# usb_serial.net
KiCad netlist of a schematic drawn in Altium Designer
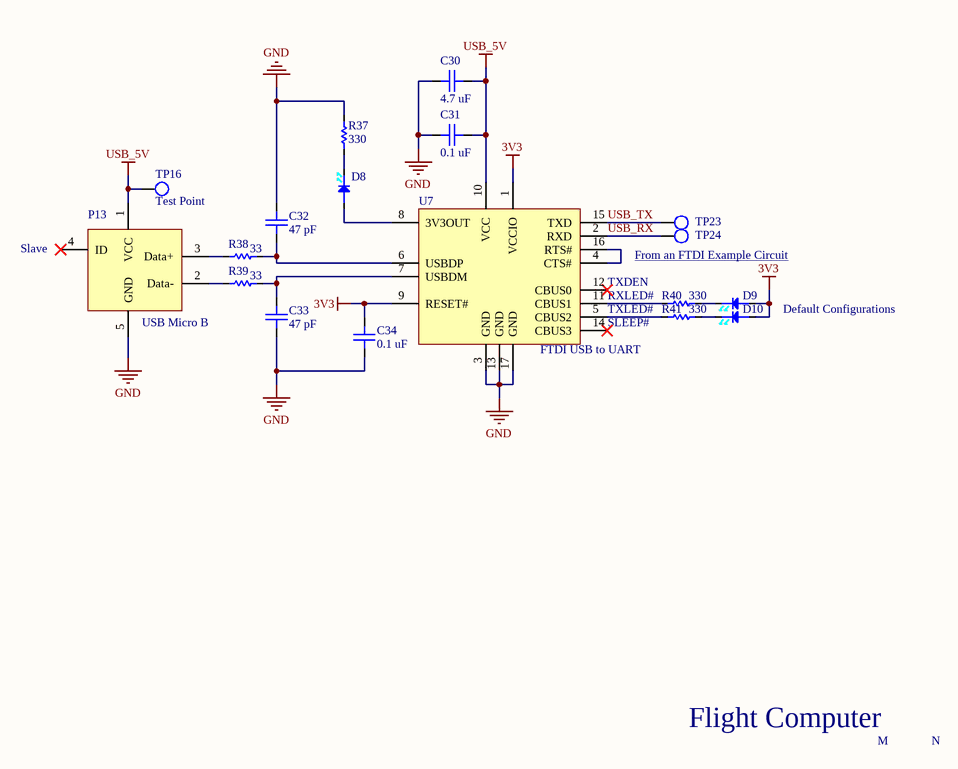
[diagram p0: usb_serial.SchDoc]

(export (version "E")
  (design (tool "Eeschema 10.0.6"))
  (components
    (comp (ref "C30")
      (value "4.7 uF")
      (footprint "CAP-CER-0805-TALL")
      (description "±10%, 0805")
      (libsource (lib "passive") (part "CAP-CER-4.7uF-10V"))
    )
    (comp (ref "C31")
      (value "0.1 uF")
      (footprint "CAP-CER-0805-SHORT")
      (description "±10%, 0805")
      (libsource (lib "passive") (part "CAP-CER-0.1uF-25V"))
    )
    (comp (ref "C32")
      (value "47 pF")
      (footprint "CAP-CER-0805-SHORT")
      (description "±5%, 0805")
      (libsource (lib "passive") (part "CAP-CER-47pF-50V"))
    )
    (comp (ref "C33")
      (value "47 pF")
      (footprint "CAP-CER-0805-SHORT")
      (description "±5%, 0805")
      (libsource (lib "passive") (part "CAP-CER-47pF-50V"))
    )
    (comp (ref "C34")
      (value "0.1 uF")
      (footprint "CAP-CER-0805-SHORT")
      (description "±10%, 0805")
      (libsource (lib "passive") (part "CAP-CER-0.1uF-25V"))
    )
    (comp (ref "D8")
      (value "LED-WHT-20mA")
      (footprint "LED-0805")
      (description "2.2V, 0805")
      (libsource (lib "passive") (part "LED-WHT-20mA"))
    )
    (comp (ref "D9")
      (value "LED-WHT-20mA")
      (footprint "LED-0805")
      (description "2.2V, 0805")
      (libsource (lib "passive") (part "LED-WHT-20mA"))
    )
    (comp (ref "D10")
      (value "LED-WHT-20mA")
      (footprint "LED-0805")
      (description "2.2V, 0805")
      (libsource (lib "passive") (part "LED-WHT-20mA"))
    )
    (comp (ref "P13")
      (value "USB Micro B")
      (footprint "USB Micro B")
      (libsource (lib "connector") (part "USB Micro B"))
    )
    (comp (ref "R37")
      (value "330")
      (footprint "RES-0805")
      (description "0805")
      (libsource (lib "passive") (part "RES-330-1/8W"))
    )
    (comp (ref "R38")
      (value "33")
      (footprint "RES-0805")
      (description "0805")
      (libsource (lib "passive") (part "RES-33-1/8W"))
    )
    (comp (ref "R39")
      (value "33")
      (footprint "RES-0805")
      (description "0805")
      (libsource (lib "passive") (part "RES-33-1/8W"))
    )
    (comp (ref "R40")
      (value "330")
      (footprint "RES-0805")
      (description "0805")
      (libsource (lib "passive") (part "RES-330-1/8W"))
    )
    (comp (ref "R41")
      (value "330")
      (footprint "RES-0805")
      (description "0805")
      (libsource (lib "passive") (part "RES-330-1/8W"))
    )
    (comp (ref "TP16")
      (value "Test Point")
      (footprint "0603 Test Point")
      (description "0603")
      (libsource (lib "passive") (part "Test Point"))
    )
    (comp (ref "TP23")
      (value "Test Point")
      (footprint "0603 Test Point")
      (description "0603")
      (libsource (lib "passive") (part "Test Point"))
    )
    (comp (ref "TP24")
      (value "Test Point")
      (footprint "0603 Test Point")
      (description "0603")
      (libsource (lib "passive") (part "Test Point"))
    )
    (comp (ref "U7")
      (value "FTDI USB to UART")
      (footprint "QFN16-0.65")
      (libsource (lib "ic") (part "FT230XQ-R"))
    )
  )
  (nets
    (net (code "1") (name "/USB_RX") (class "Default")
      (node (ref "TP24") (pin "1") (pinfunction "1_1") (pintype "passive"))
      (node (ref "U7") (pin "2") (pinfunction "RXD_2") (pintype "passive"))
    )
    (net (code "2") (name "/USB_TX") (class "Default")
      (node (ref "TP23") (pin "1") (pinfunction "1_1") (pintype "passive"))
      (node (ref "U7") (pin "15") (pinfunction "TXD_15") (pintype "passive"))
    )
    (net (code "3") (name "3V3") (class "Default")
      (node (ref "C34") (pin "2") (pinfunction "2_2") (pintype "passive"))
      (node (ref "D10") (pin "1") (pinfunction "CT_1") (pintype "passive"))
      (node (ref "D9") (pin "1") (pinfunction "CT_1") (pintype "passive"))
      (node (ref "U7") (pin "1") (pinfunction "VCCIO_1") (pintype "passive"))
      (node (ref "U7") (pin "9") (pinfunction "RESET#_9") (pintype "passive"))
    )
    (net (code "4") (name "GND") (class "Default")
      (node (ref "C30") (pin "2") (pinfunction "2_2") (pintype "passive"))
      (node (ref "C31") (pin "2") (pinfunction "2_2") (pintype "passive"))
      (node (ref "C32") (pin "2") (pinfunction "2_2") (pintype "passive"))
      (node (ref "C33") (pin "1") (pinfunction "1_1") (pintype "passive"))
      (node (ref "C34") (pin "1") (pinfunction "1_1") (pintype "passive"))
      (node (ref "P13") (pin "5") (pinfunction "GND_5") (pintype "passive"))
      (node (ref "R37") (pin "1") (pinfunction "1_1") (pintype "passive"))
      (node (ref "U7") (pin "13") (pinfunction "GND_13") (pintype "passive"))
      (node (ref "U7") (pin "17") (pinfunction "GND_17") (pintype "passive"))
      (node (ref "U7") (pin "3") (pinfunction "GND_3") (pintype "passive"))
    )
    (net (code "5") (name "Net-(D8-AN)") (class "Default")
      (node (ref "D8") (pin "2") (pinfunction "AN_2") (pintype "passive"))
      (node (ref "R37") (pin "2") (pinfunction "2_2") (pintype "passive"))
    )
    (net (code "6") (name "Net-(D8-CT)") (class "Default")
      (node (ref "D8") (pin "1") (pinfunction "CT_1") (pintype "passive"))
      (node (ref "U7") (pin "8") (pinfunction "3V3OUT_8") (pintype "passive"))
    )
    (net (code "7") (name "Net-(D9-AN)") (class "Default")
      (node (ref "D9") (pin "2") (pinfunction "AN_2") (pintype "passive"))
      (node (ref "R40") (pin "2") (pinfunction "2_2") (pintype "passive"))
    )
    (net (code "8") (name "Net-(D10-AN)") (class "Default")
      (node (ref "D10") (pin "2") (pinfunction "AN_2") (pintype "passive"))
      (node (ref "R41") (pin "2") (pinfunction "2_2") (pintype "passive"))
    )
    (net (code "9") (name "Net-(P13-Data+)") (class "Default")
      (node (ref "P13") (pin "3") (pinfunction "Data+_3") (pintype "passive"))
      (node (ref "R38") (pin "1") (pinfunction "1_1") (pintype "passive"))
    )
    (net (code "10") (name "Net-(P13-Data-)") (class "Default")
      (node (ref "P13") (pin "2") (pinfunction "Data-_2") (pintype "passive"))
      (node (ref "R39") (pin "1") (pinfunction "1_1") (pintype "passive"))
    )
    (net (code "11") (name "Net-(U7-CBUS1)") (class "Default")
      (node (ref "R40") (pin "1") (pinfunction "1_1") (pintype "passive"))
      (node (ref "U7") (pin "11") (pinfunction "CBUS1_11") (pintype "passive"))
    )
    (net (code "12") (name "Net-(U7-CBUS2)") (class "Default")
      (node (ref "R41") (pin "1") (pinfunction "1_1") (pintype "passive"))
      (node (ref "U7") (pin "5") (pinfunction "CBUS2_5") (pintype "passive"))
    )
    (net (code "13") (name "Net-(U7-CTS#)") (class "Default")
      (node (ref "U7") (pin "16") (pinfunction "RTS#_16") (pintype "passive"))
      (node (ref "U7") (pin "4") (pinfunction "CTS#_4") (pintype "passive"))
    )
    (net (code "14") (name "Net-(U7-USBDM)") (class "Default")
      (node (ref "C33") (pin "2") (pinfunction "2_2") (pintype "passive"))
      (node (ref "R39") (pin "2") (pinfunction "2_2") (pintype "passive"))
      (node (ref "U7") (pin "7") (pinfunction "USBDM_7") (pintype "passive"))
    )
    (net (code "15") (name "Net-(U7-USBDP)") (class "Default")
      (node (ref "C32") (pin "1") (pinfunction "1_1") (pintype "passive"))
      (node (ref "R38") (pin "2") (pinfunction "2_2") (pintype "passive"))
      (node (ref "U7") (pin "6") (pinfunction "USBDP_6") (pintype "passive"))
    )
    (net (code "16") (name "USB_5V") (class "Default")
      (node (ref "C30") (pin "1") (pinfunction "1_1") (pintype "passive"))
      (node (ref "C31") (pin "1") (pinfunction "1_1") (pintype "passive"))
      (node (ref "P13") (pin "1") (pinfunction "VCC_1") (pintype "passive"))
      (node (ref "TP16") (pin "1") (pinfunction "1_1") (pintype "passive"))
      (node (ref "U7") (pin "10") (pinfunction "VCC_10") (pintype "passive"))
    )
    (net (code "17") (name "unconnected-(P13-ID-Pad4)") (class "Default")
      (node (ref "P13") (pin "4") (pinfunction "ID_4") (pintype "passive+no_connect"))
    )
    (net (code "18") (name "unconnected-(U7-CBUS0-Pad12)") (class "Default")
      (node (ref "U7") (pin "12") (pinfunction "CBUS0_12") (pintype "passive+no_connect"))
    )
    (net (code "19") (name "unconnected-(U7-CBUS3-Pad14)") (class "Default")
      (node (ref "U7") (pin "14") (pinfunction "CBUS3_14") (pintype "passive+no_connect"))
    )
  )
)
